# led_dice.net
KiCad netlist of a schematic drawn in EAGLE
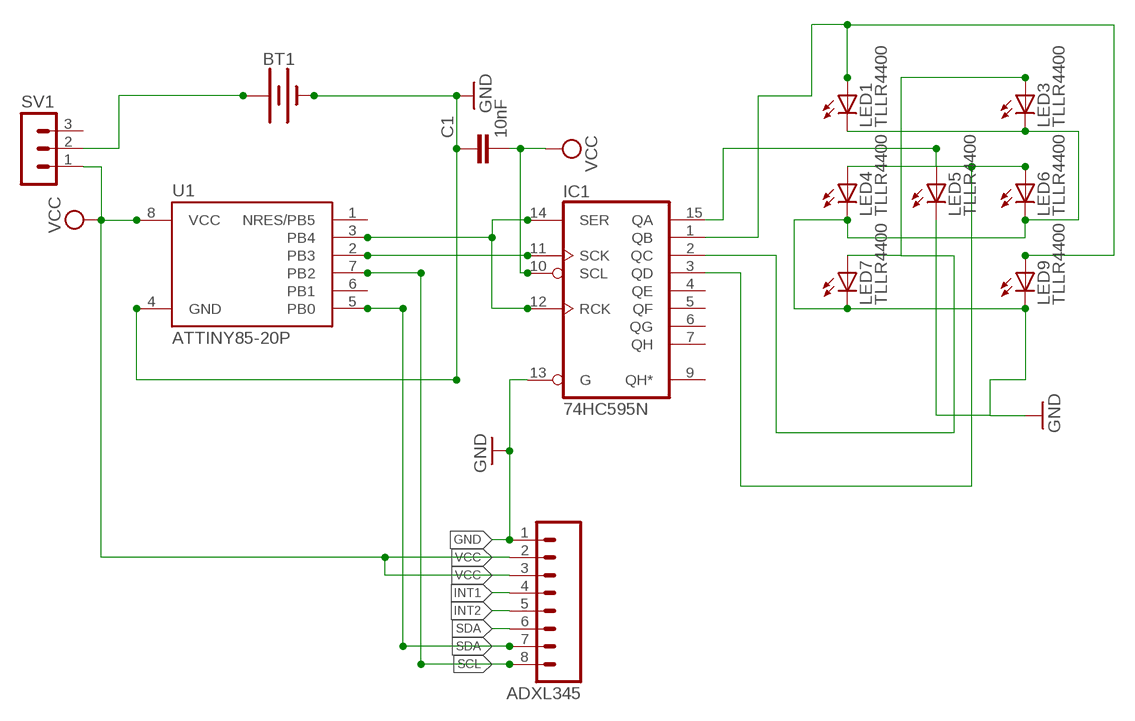
[diagram p0: schematic, sheet 1]

(export (version "E")
  (design (tool "Eeschema 10.0.6"))
  (components
    (comp (ref "ADXL345")
      (value "M08")
      (footprint "eagle-import:1X08")
      (libsource (lib "eagle-import") (part "M08"))
    )
    (comp (ref "BT1")
      (value "BATTERY-20MM_PTH")
      (footprint "eagle-import:BATTCOM_20MM_PTH")
      (libsource (lib "eagle-import") (part "BATTERY-20MM_PTH"))
    )
    (comp (ref "C1")
      (value "10nF")
      (footprint "eagle-import:C025-024X044")
      (libsource (lib "eagle-import") (part "C-EU025-024X044"))
    )
    (comp (ref "IC1")
      (value "74HC595N")
      (footprint "eagle-import:DIL16")
      (libsource (lib "eagle-import") (part "74595NHC"))
    )
    (comp (ref "LED1")
      (value "TLLR4400")
      (footprint "eagle-import:LED3MM")
      (fields (field (name "MF") "VISHAY SEMICONDUCTOR"))
      (libsource (lib "eagle-import") (part "TLLR4400"))
    )
    (comp (ref "LED3")
      (value "TLLR4400")
      (footprint "eagle-import:LED3MM")
      (fields (field (name "MF") "VISHAY SEMICONDUCTOR"))
      (libsource (lib "eagle-import") (part "TLLR4400"))
    )
    (comp (ref "LED4")
      (value "TLLR4400")
      (footprint "eagle-import:LED3MM")
      (fields (field (name "MF") "VISHAY SEMICONDUCTOR"))
      (libsource (lib "eagle-import") (part "TLLR4400"))
    )
    (comp (ref "LED5")
      (value "TLLR4400")
      (footprint "eagle-import:LED3MM")
      (fields (field (name "MF") "VISHAY SEMICONDUCTOR"))
      (libsource (lib "eagle-import") (part "TLLR4400"))
    )
    (comp (ref "LED6")
      (value "TLLR4400")
      (footprint "eagle-import:LED3MM")
      (fields (field (name "MF") "VISHAY SEMICONDUCTOR"))
      (libsource (lib "eagle-import") (part "TLLR4400"))
    )
    (comp (ref "LED7")
      (value "TLLR4400")
      (footprint "eagle-import:LED3MM")
      (fields (field (name "MF") "VISHAY SEMICONDUCTOR"))
      (libsource (lib "eagle-import") (part "TLLR4400"))
    )
    (comp (ref "LED9")
      (value "TLLR4400")
      (footprint "eagle-import:LED3MM")
      (fields (field (name "MF") "VISHAY SEMICONDUCTOR"))
      (libsource (lib "eagle-import") (part "TLLR4400"))
    )
    (comp (ref "SV1")
      (value "MA03-1")
      (footprint "eagle-import:MA03-1")
      (libsource (lib "eagle-import") (part "MA03-1"))
    )
    (comp (ref "U1")
      (value "ATTINY85-20P")
      (footprint "eagle-import:PDIP08_300MIL")
      (libsource (lib "eagle-import") (part "ATTINY85P-20"))
    )
  )
  (nets
    (net (code "1") (name "GND") (class "Default")
      (node (ref "ADXL345") (pin "1") (pinfunction "1_1") (pintype "passive"))
      (node (ref "BT1") (pin "2") (pinfunction "-_2") (pintype "power_in"))
      (node (ref "C1") (pin "1") (pinfunction "1_1") (pintype "passive"))
      (node (ref "IC1") (pin "13") (pinfunction "G_13") (pintype "input"))
      (node (ref "LED1") (pin "K") (pinfunction "C_K") (pintype "passive"))
      (node (ref "LED3") (pin "K") (pinfunction "C_K") (pintype "passive"))
      (node (ref "LED4") (pin "K") (pinfunction "C_K") (pintype "passive"))
      (node (ref "LED5") (pin "K") (pinfunction "C_K") (pintype "passive"))
      (node (ref "LED6") (pin "K") (pinfunction "C_K") (pintype "passive"))
      (node (ref "LED7") (pin "K") (pinfunction "C_K") (pintype "passive"))
      (node (ref "LED9") (pin "K") (pinfunction "C_K") (pintype "passive"))
      (node (ref "U1") (pin "4") (pinfunction "GND_4") (pintype "power_in"))
    )
    (net (code "2") (name "INT1") (class "Default")
      (node (ref "ADXL345") (pin "4") (pinfunction "4_4") (pintype "passive"))
    )
    (net (code "3") (name "INT2") (class "Default")
      (node (ref "ADXL345") (pin "5") (pinfunction "5_5") (pintype "passive"))
    )
    (net (code "4") (name "Net-(BT1-+)") (class "Default")
      (node (ref "BT1") (pin "1") (pinfunction "+_1") (pintype "power_in"))
      (node (ref "SV1") (pin "2") (pinfunction "2_2") (pintype "passive"))
    )
    (net (code "5") (name "Net-(IC1A-QA)") (class "Default")
      (node (ref "IC1") (pin "15") (pinfunction "QA_15") (pintype "tri_state"))
      (node (ref "LED5") (pin "A") (pinfunction "A_A") (pintype "passive"))
    )
    (net (code "6") (name "Net-(IC1A-QB)") (class "Default")
      (node (ref "IC1") (pin "1") (pinfunction "QB_1") (pintype "tri_state"))
      (node (ref "LED1") (pin "A") (pinfunction "A_A") (pintype "passive"))
      (node (ref "LED9") (pin "A") (pinfunction "A_A") (pintype "passive"))
    )
    (net (code "7") (name "Net-(IC1A-QC)") (class "Default")
      (node (ref "IC1") (pin "2") (pinfunction "QC_2") (pintype "tri_state"))
      (node (ref "LED3") (pin "A") (pinfunction "A_A") (pintype "passive"))
      (node (ref "LED7") (pin "A") (pinfunction "A_A") (pintype "passive"))
    )
    (net (code "8") (name "Net-(IC1A-QD)") (class "Default")
      (node (ref "IC1") (pin "3") (pinfunction "QD_3") (pintype "tri_state"))
      (node (ref "LED4") (pin "A") (pinfunction "A_A") (pintype "passive"))
      (node (ref "LED6") (pin "A") (pinfunction "A_A") (pintype "passive"))
    )
    (net (code "9") (name "Net-(IC1A-RCK)") (class "Default")
      (node (ref "IC1") (pin "12") (pinfunction "RCK_12") (pintype "input"))
      (node (ref "IC1") (pin "14") (pinfunction "SER_14") (pintype "input"))
      (node (ref "U1") (pin "3") (pinfunction "PB4_3") (pintype "bidirectional"))
    )
    (net (code "10") (name "Net-(IC1A-SCK)") (class "Default")
      (node (ref "IC1") (pin "11") (pinfunction "SCK_11") (pintype "input"))
      (node (ref "U1") (pin "2") (pinfunction "PB3_2") (pintype "bidirectional"))
    )
    (net (code "11") (name "SCL") (class "Default")
      (node (ref "ADXL345") (pin "8") (pinfunction "8_8") (pintype "passive"))
      (node (ref "U1") (pin "7") (pinfunction "PB2_7") (pintype "bidirectional"))
    )
    (net (code "12") (name "SDA") (class "Default")
      (node (ref "ADXL345") (pin "7") (pinfunction "7_7") (pintype "passive"))
      (node (ref "U1") (pin "5") (pinfunction "PB0_5") (pintype "bidirectional"))
    )
    (net (code "13") (name "VCC") (class "Default")
      (node (ref "ADXL345") (pin "2") (pinfunction "2_2") (pintype "passive"))
      (node (ref "ADXL345") (pin "3") (pinfunction "3_3") (pintype "passive"))
      (node (ref "C1") (pin "2") (pinfunction "2_2") (pintype "passive"))
      (node (ref "IC1") (pin "10") (pinfunction "SCL_10") (pintype "input"))
      (node (ref "SV1") (pin "1") (pinfunction "1_1") (pintype "passive"))
      (node (ref "U1") (pin "8") (pinfunction "VCC_8") (pintype "power_in"))
    )
    (net (code "14") (name "unconnected-(ADXL345-Pad6)") (class "Default")
      (node (ref "ADXL345") (pin "6") (pinfunction "6_6") (pintype "passive"))
    )
    (net (code "15") (name "unconnected-(IC1A-QE-Pad4)") (class "Default")
      (node (ref "IC1") (pin "4") (pinfunction "QE_4") (pintype "tri_state"))
    )
    (net (code "16") (name "unconnected-(IC1A-QF-Pad5)") (class "Default")
      (node (ref "IC1") (pin "5") (pinfunction "QF_5") (pintype "tri_state"))
    )
    (net (code "17") (name "unconnected-(IC1A-QG-Pad6)") (class "Default")
      (node (ref "IC1") (pin "6") (pinfunction "QG_6") (pintype "tri_state"))
    )
    (net (code "18") (name "unconnected-(IC1A-QH*-Pad9)") (class "Default")
      (node (ref "IC1") (pin "9") (pinfunction "QH*_9") (pintype "tri_state"))
    )
    (net (code "19") (name "unconnected-(IC1A-QH-Pad7)") (class "Default")
      (node (ref "IC1") (pin "7") (pinfunction "QH_7") (pintype "tri_state"))
    )
    (net (code "20") (name "unconnected-(SV1-Pad3)") (class "Default")
      (node (ref "SV1") (pin "3") (pinfunction "3_3") (pintype "passive"))
    )
    (net (code "21") (name "unconnected-(U1-NRES{slash}PB5-Pad1)") (class "Default")
      (node (ref "U1") (pin "1") (pinfunction "NRES/PB5_1") (pintype "bidirectional"))
    )
    (net (code "22") (name "unconnected-(U1-PB1-Pad6)") (class "Default")
      (node (ref "U1") (pin "6") (pinfunction "PB1_6") (pintype "bidirectional"))
    )
  )
)
